# merch-hat.net
KiCad netlist of a schematic drawn in EAGLE
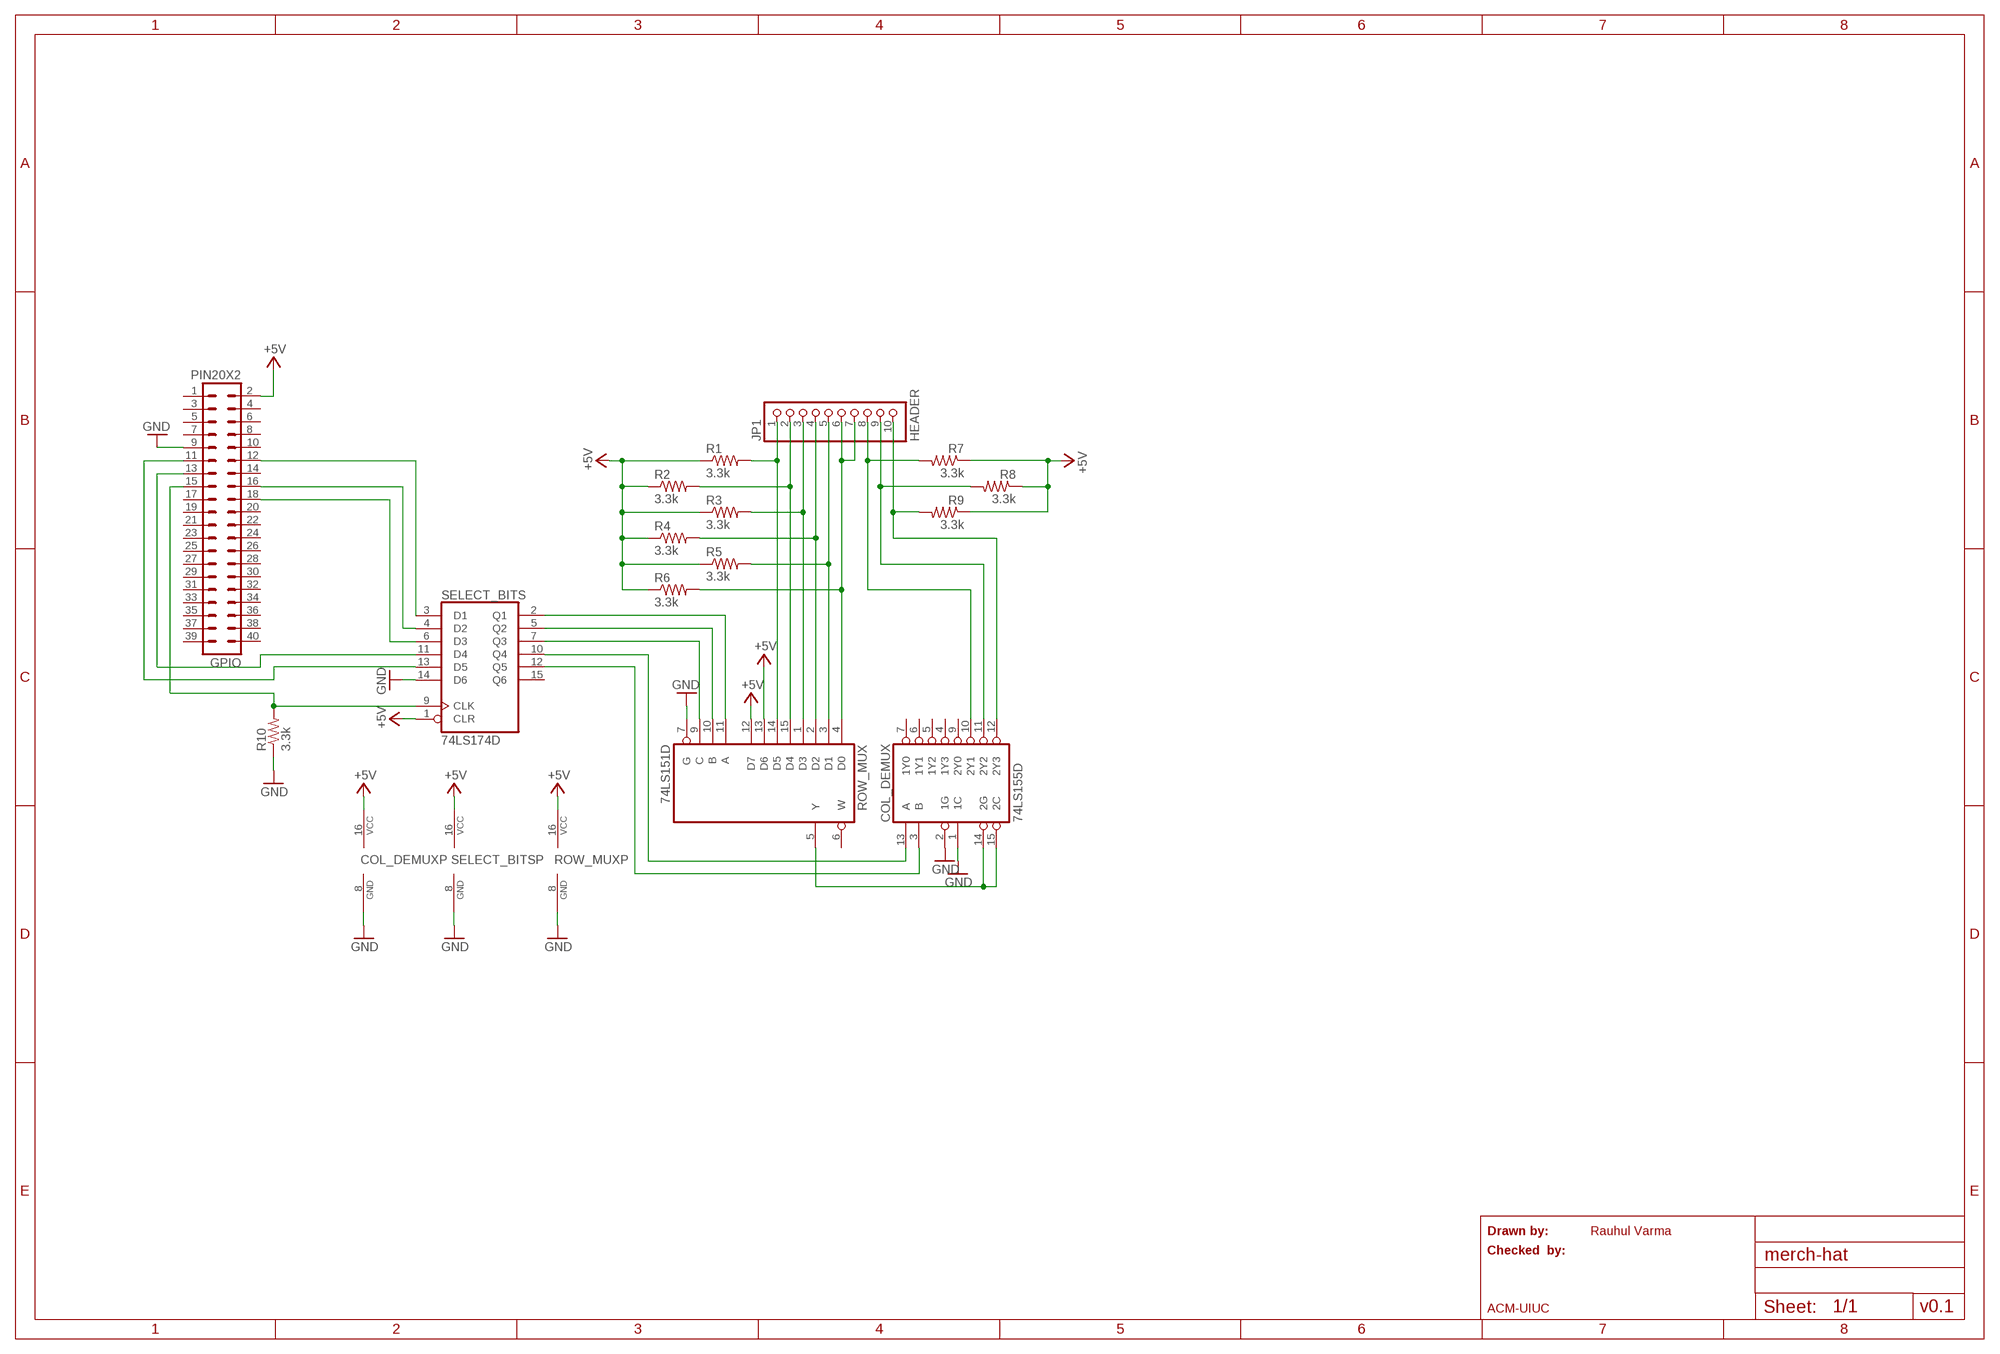
[diagram p0: schematic, sheet 1]

(export (version "E")
  (design (tool "Eeschema 10.0.6"))
  (components
    (comp (ref "COL_DEMUX")
      (value "74LS155D")
      (footprint "eagle-import:SO16")
      (libsource (lib "eagle-import") (part "74155DLS"))
    )
    (comp (ref "GPIO")
      (value "PIN20X2")
      (footprint "eagle-import:PIN_20X2")
      (libsource (lib "eagle-import") (part "PIN20X2"))
    )
    (comp (ref "JP1")
      (value "HEADER")
      (footprint "eagle-import:1X10")
      (libsource (lib "eagle-import") (part "PINHD-1X10"))
    )
    (comp (ref "R1")
      (value "3.3k")
      (footprint "eagle-import:R0805")
      (libsource (lib "eagle-import") (part "R-US_R0805"))
    )
    (comp (ref "R2")
      (value "3.3k")
      (footprint "eagle-import:R0805")
      (libsource (lib "eagle-import") (part "R-US_R0805"))
    )
    (comp (ref "R3")
      (value "3.3k")
      (footprint "eagle-import:R0805")
      (libsource (lib "eagle-import") (part "R-US_R0805"))
    )
    (comp (ref "R4")
      (value "3.3k")
      (footprint "eagle-import:R0805")
      (libsource (lib "eagle-import") (part "R-US_R0805"))
    )
    (comp (ref "R5")
      (value "3.3k")
      (footprint "eagle-import:R0805")
      (libsource (lib "eagle-import") (part "R-US_R0805"))
    )
    (comp (ref "R6")
      (value "3.3k")
      (footprint "eagle-import:R0805")
      (libsource (lib "eagle-import") (part "R-US_R0805"))
    )
    (comp (ref "R7")
      (value "3.3k")
      (footprint "eagle-import:R0805")
      (libsource (lib "eagle-import") (part "R-US_R0805"))
    )
    (comp (ref "R8")
      (value "3.3k")
      (footprint "eagle-import:R0805")
      (libsource (lib "eagle-import") (part "R-US_R0805"))
    )
    (comp (ref "R9")
      (value "3.3k")
      (footprint "eagle-import:R0805")
      (libsource (lib "eagle-import") (part "R-US_R0805"))
    )
    (comp (ref "R10")
      (value "3.3k")
      (footprint "eagle-import:R0805")
      (libsource (lib "eagle-import") (part "R-US_R0805"))
    )
    (comp (ref "ROW_MUX")
      (value "74LS151D")
      (footprint "eagle-import:SO16")
      (libsource (lib "eagle-import") (part "74151DLS"))
    )
    (comp (ref "SELECT_BITS")
      (value "74LS174D")
      (footprint "eagle-import:SO16")
      (libsource (lib "eagle-import") (part "74174DLS"))
    )
  )
  (nets
    (net (code "1") (name "+5V") (class "Default")
      (node (ref "COL_DEMUX") (pin "16") (pinfunction "VCC_16") (pintype "power_in"))
      (node (ref "GPIO") (pin "2") (pinfunction "2_2") (pintype "passive"))
      (node (ref "R1") (pin "1") (pinfunction "1_1") (pintype "passive"))
      (node (ref "R2") (pin "1") (pinfunction "1_1") (pintype "passive"))
      (node (ref "R3") (pin "1") (pinfunction "1_1") (pintype "passive"))
      (node (ref "R4") (pin "1") (pinfunction "1_1") (pintype "passive"))
      (node (ref "R5") (pin "1") (pinfunction "1_1") (pintype "passive"))
      (node (ref "R6") (pin "1") (pinfunction "1_1") (pintype "passive"))
      (node (ref "R7") (pin "1") (pinfunction "1_1") (pintype "passive"))
      (node (ref "R8") (pin "1") (pinfunction "1_1") (pintype "passive"))
      (node (ref "R9") (pin "1") (pinfunction "1_1") (pintype "passive"))
      (node (ref "ROW_MUX") (pin "12") (pinfunction "D7_12") (pintype "input"))
      (node (ref "ROW_MUX") (pin "13") (pinfunction "D6_13") (pintype "input"))
      (node (ref "ROW_MUX") (pin "16") (pinfunction "VCC_16") (pintype "power_in"))
      (node (ref "SELECT_BITS") (pin "1") (pinfunction "CLR_1") (pintype "input"))
      (node (ref "SELECT_BITS") (pin "16") (pinfunction "VCC_16") (pintype "power_in"))
    )
    (net (code "2") (name "GND") (class "Default")
      (node (ref "COL_DEMUX") (pin "1") (pinfunction "1C_1") (pintype "input"))
      (node (ref "COL_DEMUX") (pin "2") (pinfunction "1G_2") (pintype "input"))
      (node (ref "COL_DEMUX") (pin "8") (pinfunction "GND_8") (pintype "power_in"))
      (node (ref "GPIO") (pin "9") (pinfunction "9_9") (pintype "passive"))
      (node (ref "R10") (pin "1") (pinfunction "1_1") (pintype "passive"))
      (node (ref "ROW_MUX") (pin "7") (pinfunction "G_7") (pintype "input"))
      (node (ref "ROW_MUX") (pin "8") (pinfunction "GND_8") (pintype "power_in"))
      (node (ref "SELECT_BITS") (pin "14") (pinfunction "D6_14") (pintype "input"))
      (node (ref "SELECT_BITS") (pin "8") (pinfunction "GND_8") (pintype "power_in"))
    )
    (net (code "3") (name "Net-(COL_DEMUXA-2C)") (class "Default")
      (node (ref "COL_DEMUX") (pin "14") (pinfunction "2G_14") (pintype "input"))
      (node (ref "COL_DEMUX") (pin "15") (pinfunction "2C_15") (pintype "input"))
      (node (ref "ROW_MUX") (pin "5") (pinfunction "Y_5") (pintype "output"))
    )
    (net (code "4") (name "Net-(COL_DEMUXA-2Y1)") (class "Default")
      (node (ref "COL_DEMUX") (pin "10") (pinfunction "2Y1_10") (pintype "output"))
      (node (ref "JP1") (pin "8") (pinfunction "8_8") (pintype "passive"))
      (node (ref "R7") (pin "2") (pinfunction "2_2") (pintype "passive"))
    )
    (net (code "5") (name "Net-(COL_DEMUXA-2Y2)") (class "Default")
      (node (ref "COL_DEMUX") (pin "11") (pinfunction "2Y2_11") (pintype "output"))
      (node (ref "JP1") (pin "9") (pinfunction "9_9") (pintype "passive"))
      (node (ref "R8") (pin "2") (pinfunction "2_2") (pintype "passive"))
    )
    (net (code "6") (name "Net-(COL_DEMUXA-2Y3)") (class "Default")
      (node (ref "COL_DEMUX") (pin "12") (pinfunction "2Y3_12") (pintype "output"))
      (node (ref "JP1") (pin "10") (pinfunction "10_10") (pintype "passive"))
      (node (ref "R9") (pin "2") (pinfunction "2_2") (pintype "passive"))
    )
    (net (code "7") (name "Net-(COL_DEMUXA-A)") (class "Default")
      (node (ref "COL_DEMUX") (pin "13") (pinfunction "A_13") (pintype "input"))
      (node (ref "SELECT_BITS") (pin "10") (pinfunction "Q4_10") (pintype "output"))
    )
    (net (code "8") (name "Net-(COL_DEMUXA-B)") (class "Default")
      (node (ref "COL_DEMUX") (pin "3") (pinfunction "B_3") (pintype "input"))
      (node (ref "SELECT_BITS") (pin "12") (pinfunction "Q5_12") (pintype "output"))
    )
    (net (code "9") (name "Net-(ROW_MUXA-A)") (class "Default")
      (node (ref "ROW_MUX") (pin "11") (pinfunction "A_11") (pintype "input"))
      (node (ref "SELECT_BITS") (pin "2") (pinfunction "Q1_2") (pintype "output"))
    )
    (net (code "10") (name "Net-(ROW_MUXA-B)") (class "Default")
      (node (ref "ROW_MUX") (pin "10") (pinfunction "B_10") (pintype "input"))
      (node (ref "SELECT_BITS") (pin "5") (pinfunction "Q2_5") (pintype "output"))
    )
    (net (code "11") (name "Net-(ROW_MUXA-C)") (class "Default")
      (node (ref "ROW_MUX") (pin "9") (pinfunction "C_9") (pintype "input"))
      (node (ref "SELECT_BITS") (pin "7") (pinfunction "Q3_7") (pintype "output"))
    )
    (net (code "12") (name "Net-(ROW_MUXA-D0)") (class "Default")
      (node (ref "JP1") (pin "6") (pinfunction "6_6") (pintype "passive"))
      (node (ref "JP1") (pin "7") (pinfunction "7_7") (pintype "passive"))
      (node (ref "R6") (pin "2") (pinfunction "2_2") (pintype "passive"))
      (node (ref "ROW_MUX") (pin "4") (pinfunction "D0_4") (pintype "input"))
    )
    (net (code "13") (name "Net-(ROW_MUXA-D1)") (class "Default")
      (node (ref "JP1") (pin "5") (pinfunction "5_5") (pintype "passive"))
      (node (ref "R5") (pin "2") (pinfunction "2_2") (pintype "passive"))
      (node (ref "ROW_MUX") (pin "3") (pinfunction "D1_3") (pintype "input"))
    )
    (net (code "14") (name "Net-(ROW_MUXA-D2)") (class "Default")
      (node (ref "JP1") (pin "4") (pinfunction "4_4") (pintype "passive"))
      (node (ref "R4") (pin "2") (pinfunction "2_2") (pintype "passive"))
      (node (ref "ROW_MUX") (pin "2") (pinfunction "D2_2") (pintype "input"))
    )
    (net (code "15") (name "Net-(ROW_MUXA-D3)") (class "Default")
      (node (ref "JP1") (pin "3") (pinfunction "3_3") (pintype "passive"))
      (node (ref "R3") (pin "2") (pinfunction "2_2") (pintype "passive"))
      (node (ref "ROW_MUX") (pin "1") (pinfunction "D3_1") (pintype "input"))
    )
    (net (code "16") (name "Net-(ROW_MUXA-D4)") (class "Default")
      (node (ref "JP1") (pin "2") (pinfunction "2_2") (pintype "passive"))
      (node (ref "R2") (pin "2") (pinfunction "2_2") (pintype "passive"))
      (node (ref "ROW_MUX") (pin "15") (pinfunction "D4_15") (pintype "input"))
    )
    (net (code "17") (name "Net-(ROW_MUXA-D5)") (class "Default")
      (node (ref "JP1") (pin "1") (pinfunction "1_1") (pintype "passive"))
      (node (ref "R1") (pin "2") (pinfunction "2_2") (pintype "passive"))
      (node (ref "ROW_MUX") (pin "14") (pinfunction "D5_14") (pintype "input"))
    )
    (net (code "18") (name "Net-(SELECT_BITSA-CLK)") (class "Default")
      (node (ref "GPIO") (pin "15") (pinfunction "15_15") (pintype "passive"))
      (node (ref "R10") (pin "2") (pinfunction "2_2") (pintype "passive"))
      (node (ref "SELECT_BITS") (pin "9") (pinfunction "CLK_9") (pintype "input"))
    )
    (net (code "19") (name "Net-(SELECT_BITSA-D1)") (class "Default")
      (node (ref "GPIO") (pin "12") (pinfunction "12_12") (pintype "passive"))
      (node (ref "SELECT_BITS") (pin "3") (pinfunction "D1_3") (pintype "input"))
    )
    (net (code "20") (name "Net-(SELECT_BITSA-D2)") (class "Default")
      (node (ref "GPIO") (pin "16") (pinfunction "16_16") (pintype "passive"))
      (node (ref "SELECT_BITS") (pin "4") (pinfunction "D2_4") (pintype "input"))
    )
    (net (code "21") (name "Net-(SELECT_BITSA-D3)") (class "Default")
      (node (ref "GPIO") (pin "18") (pinfunction "18_18") (pintype "passive"))
      (node (ref "SELECT_BITS") (pin "6") (pinfunction "D3_6") (pintype "input"))
    )
    (net (code "22") (name "Net-(SELECT_BITSA-D4)") (class "Default")
      (node (ref "GPIO") (pin "13") (pinfunction "13_13") (pintype "passive"))
      (node (ref "SELECT_BITS") (pin "11") (pinfunction "D4_11") (pintype "input"))
    )
    (net (code "23") (name "Net-(SELECT_BITSA-D5)") (class "Default")
      (node (ref "GPIO") (pin "11") (pinfunction "11_11") (pintype "passive"))
      (node (ref "SELECT_BITS") (pin "13") (pinfunction "D5_13") (pintype "input"))
    )
    (net (code "24") (name "unconnected-(COL_DEMUXA-1Y0-Pad7)") (class "Default")
      (node (ref "COL_DEMUX") (pin "7") (pinfunction "1Y0_7") (pintype "output"))
    )
    (net (code "25") (name "unconnected-(COL_DEMUXA-1Y1-Pad6)") (class "Default")
      (node (ref "COL_DEMUX") (pin "6") (pinfunction "1Y1_6") (pintype "output"))
    )
    (net (code "26") (name "unconnected-(COL_DEMUXA-1Y2-Pad5)") (class "Default")
      (node (ref "COL_DEMUX") (pin "5") (pinfunction "1Y2_5") (pintype "output"))
    )
    (net (code "27") (name "unconnected-(COL_DEMUXA-1Y3-Pad4)") (class "Default")
      (node (ref "COL_DEMUX") (pin "4") (pinfunction "1Y3_4") (pintype "output"))
    )
    (net (code "28") (name "unconnected-(COL_DEMUXA-2Y0-Pad9)") (class "Default")
      (node (ref "COL_DEMUX") (pin "9") (pinfunction "2Y0_9") (pintype "output"))
    )
    (net (code "29") (name "unconnected-(GPIO-Pad1)") (class "Default")
      (node (ref "GPIO") (pin "1") (pinfunction "1_1") (pintype "passive"))
    )
    (net (code "30") (name "unconnected-(GPIO-Pad3)") (class "Default")
      (node (ref "GPIO") (pin "3") (pinfunction "3_3") (pintype "passive"))
    )
    (net (code "31") (name "unconnected-(GPIO-Pad4)") (class "Default")
      (node (ref "GPIO") (pin "4") (pinfunction "4_4") (pintype "passive"))
    )
    (net (code "32") (name "unconnected-(GPIO-Pad5)") (class "Default")
      (node (ref "GPIO") (pin "5") (pinfunction "5_5") (pintype "passive"))
    )
    (net (code "33") (name "unconnected-(GPIO-Pad6)") (class "Default")
      (node (ref "GPIO") (pin "6") (pinfunction "6_6") (pintype "passive"))
    )
    (net (code "34") (name "unconnected-(GPIO-Pad7)") (class "Default")
      (node (ref "GPIO") (pin "7") (pinfunction "7_7") (pintype "passive"))
    )
    (net (code "35") (name "unconnected-(GPIO-Pad8)") (class "Default")
      (node (ref "GPIO") (pin "8") (pinfunction "8_8") (pintype "passive"))
    )
    (net (code "36") (name "unconnected-(GPIO-Pad10)") (class "Default")
      (node (ref "GPIO") (pin "10") (pinfunction "10_10") (pintype "passive"))
    )
    (net (code "37") (name "unconnected-(GPIO-Pad14)") (class "Default")
      (node (ref "GPIO") (pin "14") (pinfunction "14_14") (pintype "passive"))
    )
    (net (code "38") (name "unconnected-(GPIO-Pad17)") (class "Default")
      (node (ref "GPIO") (pin "17") (pinfunction "17_17") (pintype "passive"))
    )
    (net (code "39") (name "unconnected-(GPIO-Pad19)") (class "Default")
      (node (ref "GPIO") (pin "19") (pinfunction "19_19") (pintype "passive"))
    )
    (net (code "40") (name "unconnected-(GPIO-Pad20)") (class "Default")
      (node (ref "GPIO") (pin "20") (pinfunction "20_20") (pintype "passive"))
    )
    (net (code "41") (name "unconnected-(GPIO-Pad21)") (class "Default")
      (node (ref "GPIO") (pin "21") (pinfunction "21_21") (pintype "passive"))
    )
    (net (code "42") (name "unconnected-(GPIO-Pad22)") (class "Default")
      (node (ref "GPIO") (pin "22") (pinfunction "22_22") (pintype "passive"))
    )
    (net (code "43") (name "unconnected-(GPIO-Pad23)") (class "Default")
      (node (ref "GPIO") (pin "23") (pinfunction "23_23") (pintype "passive"))
    )
    (net (code "44") (name "unconnected-(GPIO-Pad24)") (class "Default")
      (node (ref "GPIO") (pin "24") (pinfunction "24_24") (pintype "passive"))
    )
    (net (code "45") (name "unconnected-(GPIO-Pad25)") (class "Default")
      (node (ref "GPIO") (pin "25") (pinfunction "25_25") (pintype "passive"))
    )
    (net (code "46") (name "unconnected-(GPIO-Pad26)") (class "Default")
      (node (ref "GPIO") (pin "26") (pinfunction "26_26") (pintype "passive"))
    )
    (net (code "47") (name "unconnected-(GPIO-Pad27)") (class "Default")
      (node (ref "GPIO") (pin "27") (pinfunction "27_27") (pintype "passive"))
    )
    (net (code "48") (name "unconnected-(GPIO-Pad28)") (class "Default")
      (node (ref "GPIO") (pin "28") (pinfunction "28_28") (pintype "passive"))
    )
    (net (code "49") (name "unconnected-(GPIO-Pad29)") (class "Default")
      (node (ref "GPIO") (pin "29") (pinfunction "29_29") (pintype "passive"))
    )
    (net (code "50") (name "unconnected-(GPIO-Pad30)") (class "Default")
      (node (ref "GPIO") (pin "30") (pinfunction "30_30") (pintype "passive"))
    )
    (net (code "51") (name "unconnected-(GPIO-Pad31)") (class "Default")
      (node (ref "GPIO") (pin "31") (pinfunction "31_31") (pintype "passive"))
    )
    (net (code "52") (name "unconnected-(GPIO-Pad32)") (class "Default")
      (node (ref "GPIO") (pin "32") (pinfunction "32_32") (pintype "passive"))
    )
    (net (code "53") (name "unconnected-(GPIO-Pad33)") (class "Default")
      (node (ref "GPIO") (pin "33") (pinfunction "33_33") (pintype "passive"))
    )
    (net (code "54") (name "unconnected-(GPIO-Pad34)") (class "Default")
      (node (ref "GPIO") (pin "34") (pinfunction "34_34") (pintype "passive"))
    )
    (net (code "55") (name "unconnected-(GPIO-Pad35)") (class "Default")
      (node (ref "GPIO") (pin "35") (pinfunction "35_35") (pintype "passive"))
    )
    (net (code "56") (name "unconnected-(GPIO-Pad36)") (class "Default")
      (node (ref "GPIO") (pin "36") (pinfunction "36_36") (pintype "passive"))
    )
    (net (code "57") (name "unconnected-(GPIO-Pad37)") (class "Default")
      (node (ref "GPIO") (pin "37") (pinfunction "37_37") (pintype "passive"))
    )
    (net (code "58") (name "unconnected-(GPIO-Pad38)") (class "Default")
      (node (ref "GPIO") (pin "38") (pinfunction "38_38") (pintype "passive"))
    )
    (net (code "59") (name "unconnected-(GPIO-Pad39)") (class "Default")
      (node (ref "GPIO") (pin "39") (pinfunction "39_39") (pintype "passive"))
    )
    (net (code "60") (name "unconnected-(GPIO-Pad40)") (class "Default")
      (node (ref "GPIO") (pin "40") (pinfunction "40_40") (pintype "passive"))
    )
    (net (code "61") (name "unconnected-(ROW_MUXA-W-Pad6)") (class "Default")
      (node (ref "ROW_MUX") (pin "6") (pinfunction "W_6") (pintype "output"))
    )
    (net (code "62") (name "unconnected-(SELECT_BITSA-Q6-Pad15)") (class "Default")
      (node (ref "SELECT_BITS") (pin "15") (pinfunction "Q6_15") (pintype "output"))
    )
  )
)
